# Power.net
KiCad netlist of a schematic drawn in Altium Designer
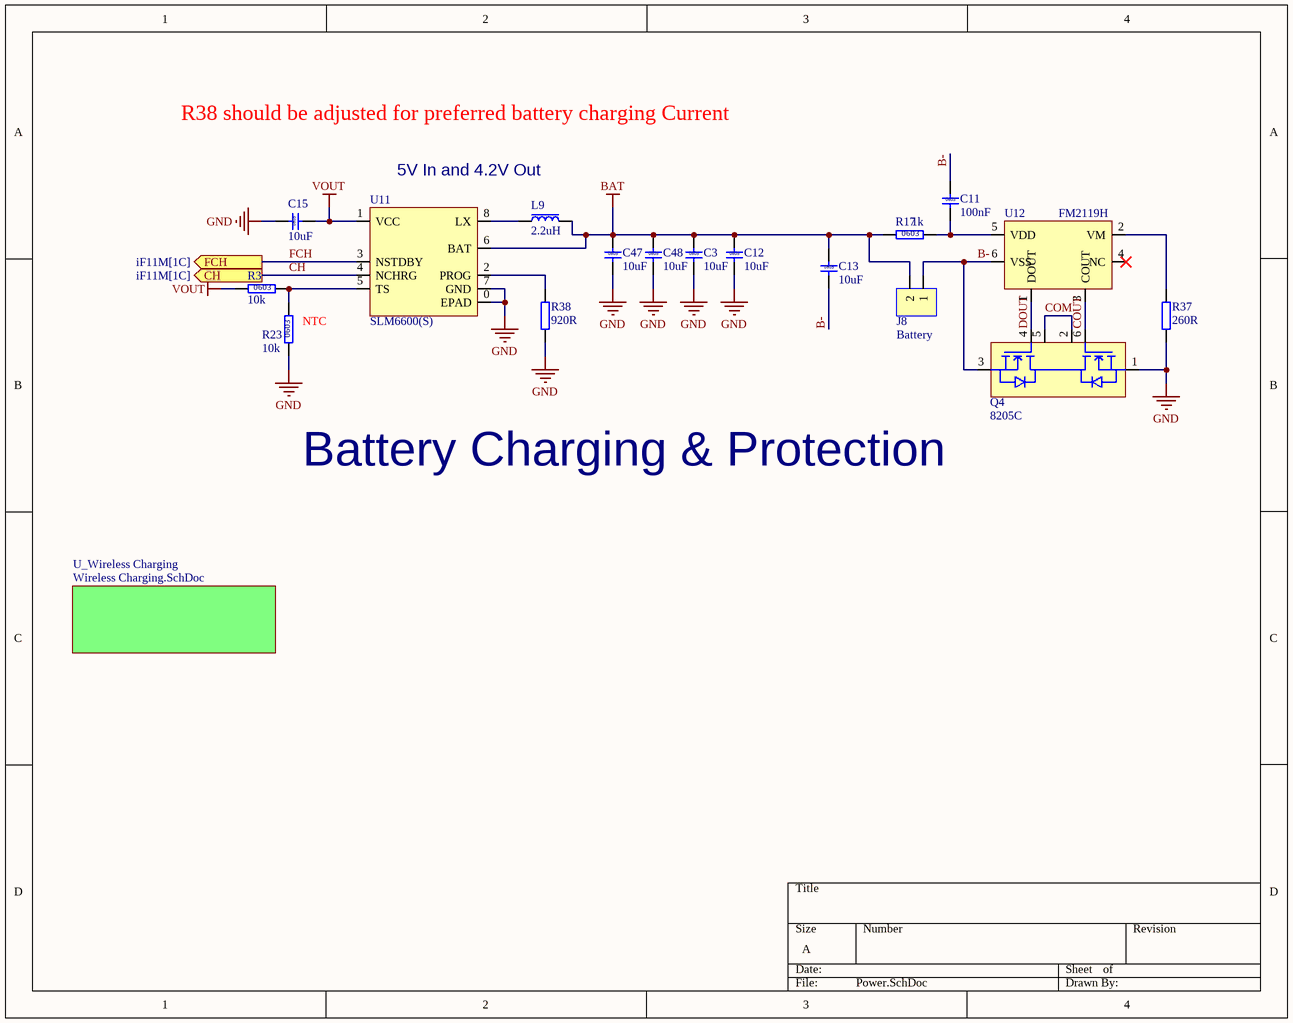
[diagram p0: Power.SchDoc]

(export (version "E")
  (design (tool "Eeschema 10.0.6"))
  (components
    (comp (ref "C3")
      (value "10uF")
      (footprint "C0805")
      (description "10% 16V")
      (fields (field (name "PART NO") "WP0005367"))
      (libsource (lib "Rescap") (part "C 0805 22uF 16V"))
    )
    (comp (ref "C11")
      (value "100nF")
      (footprint "C0603")
      (description "10% 50V")
      (fields (field (name "PART NO") "W-T-CA-X703N100K50VNT") (field (name "MANUFACTURER") "FENGHUA"))
      (libsource (lib "Rescap") (part "C 0603 100nF 50V"))
    )
    (comp (ref "C12")
      (value "10uF")
      (footprint "C0805")
      (description "10% 16V")
      (fields (field (name "PART NO") "WP0005367"))
      (libsource (lib "Rescap") (part "C 0805 22uF 16V"))
    )
    (comp (ref "C13")
      (value "10uF")
      (footprint "C0805")
      (description "10% 16V")
      (fields (field (name "PART NO") "WP0005367"))
      (libsource (lib "Rescap") (part "C 0805 22uF 16V"))
    )
    (comp (ref "C15")
      (value "10uF")
      (footprint "C0805")
      (description "10% 25V")
      (fields (field (name "PART NO") "WP0005368"))
      (libsource (lib "Rescap") (part "C 0805 10uF 25V"))
    )
    (comp (ref "C47")
      (value "10uF")
      (footprint "C0805")
      (description "10% 16V")
      (fields (field (name "PART NO") "WP0005367"))
      (libsource (lib "Rescap") (part "C 0805 22uF 16V"))
    )
    (comp (ref "C48")
      (value "10uF")
      (footprint "C0805")
      (description "10% 16V")
      (fields (field (name "PART NO") "WP0005367"))
      (libsource (lib "Rescap") (part "C 0805 22uF 16V"))
    )
    (comp (ref "J8")
      (value "Battery")
      (footprint "B2B-PH-2mm")
      (description "B2B PH 1X2 2 Pin B2B Connector")
      (libsource (lib "Connector") (part "B2B-PH-2MM"))
    )
    (comp (ref "L9")
      (value "2.2uH")
      (footprint "CD54")
      (description "SMD Inductor 2.2 uH CD54")
      (libsource (lib "Inductor") (part "CD54"))
    )
    (comp (ref "Q4")
      (value "8205C")
      (footprint "SOT23-6")
      (description "20V N-channel enhancement MOS field effect transistor")
      (libsource (lib "Transistor") (part "JST8205S"))
    )
    (comp (ref "R3")
      (value "10k")
      (footprint "R0603-LD")
      (description "5%")
      (fields (field (name "PART NO") "W-T-RE-RS03K103JT") (field (name "MANUFACTURER") "热敏D541V11增加1颗用量"))
      (libsource (lib "Rescap") (part "R 0603 10k"))
    )
    (comp (ref "R17")
      (value "1k")
      (footprint "R0603-LD")
      (description "5%")
      (fields (field (name "PART NO") "W-T-RE-RS03K102JT") (field (name "MANUFACTURER") "LAGEO"))
      (libsource (lib "Rescap") (part "R 0603 1k"))
    )
    (comp (ref "R23")
      (value "10k")
      (footprint "R0603-LD")
      (description "5%")
      (fields (field (name "PART NO") "W-T-RE-RS03K103JT") (field (name "MANUFACTURER") "热敏D541V11增加1颗用量"))
      (libsource (lib "Rescap") (part "R 0603 10k"))
    )
    (comp (ref "R37") (value "260R") (footprint "R0603") (libsource (lib "Resistor") (part "Resistor")))
    (comp (ref "R38") (value "920R") (footprint "R0603") (libsource (lib "Resistor") (part "Resistor")))
    (comp (ref "U11")
      (value "SLM6600(S)")
      (footprint "SOP-8 - EPAD")
      (libsource (lib "mylib2") (part "SLM6600(S)"))
    )
    (comp (ref "U12") (value "FM2119H") (footprint "SOT23-6") (libsource (lib "mylib2") (part "FM2119H")))
  )
  (nets
    (net (code "1") (name "/B-") (class "Default")
      (node (ref "C11") (pin "1") (pinfunction "1_1") (pintype "passive"))
      (node (ref "C13") (pin "2") (pinfunction "2_2") (pintype "passive"))
      (node (ref "J8") (pin "1") (pinfunction "1_1") (pintype "passive"))
      (node (ref "Q4") (pin "3") (pinfunction "S2_3") (pintype "passive"))
      (node (ref "U12") (pin "6") (pinfunction "VSS_6") (pintype "passive"))
    )
    (net (code "2") (name "/CH") (class "Default")
      (node (ref "U11") (pin "4") (pinfunction "NCHRG_4") (pintype "passive"))
    )
    (net (code "3") (name "/COM") (class "Default")
      (node (ref "Q4") (pin "2") (pinfunction "D1_2") (pintype "passive"))
      (node (ref "Q4") (pin "5") (pinfunction "D2_5") (pintype "passive"))
    )
    (net (code "4") (name "/COUT") (class "Default")
      (node (ref "Q4") (pin "6") (pinfunction "G1_6") (pintype "passive"))
      (node (ref "U12") (pin "3") (pinfunction "COUT_3") (pintype "passive"))
    )
    (net (code "5") (name "/DOUT") (class "Default")
      (node (ref "Q4") (pin "4") (pinfunction "G2_4") (pintype "passive"))
      (node (ref "U12") (pin "1") (pinfunction "DOUT_1") (pintype "passive"))
    )
    (net (code "6") (name "/FCH") (class "Default")
      (node (ref "U11") (pin "3") (pinfunction "NSTDBY_3") (pintype "passive"))
    )
    (net (code "7") (name "BAT") (class "Default")
      (node (ref "C12") (pin "1") (pinfunction "1_1") (pintype "passive"))
      (node (ref "C13") (pin "1") (pinfunction "1_1") (pintype "passive"))
      (node (ref "C3") (pin "1") (pinfunction "1_1") (pintype "passive"))
      (node (ref "C47") (pin "1") (pinfunction "1_1") (pintype "passive"))
      (node (ref "C48") (pin "1") (pinfunction "1_1") (pintype "passive"))
      (node (ref "J8") (pin "2") (pinfunction "2_2") (pintype "passive"))
      (node (ref "L9") (pin "2") (pinfunction "2_2") (pintype "passive"))
      (node (ref "R17") (pin "1") (pinfunction "1_1") (pintype "passive"))
      (node (ref "U11") (pin "6") (pinfunction "BAT_6") (pintype "passive"))
    )
    (net (code "8") (name "GND") (class "Default")
      (node (ref "C12") (pin "2") (pinfunction "2_2") (pintype "passive"))
      (node (ref "C15") (pin "1") (pinfunction "1_1") (pintype "passive"))
      (node (ref "C3") (pin "2") (pinfunction "2_2") (pintype "passive"))
      (node (ref "C47") (pin "2") (pinfunction "2_2") (pintype "passive"))
      (node (ref "C48") (pin "2") (pinfunction "2_2") (pintype "passive"))
      (node (ref "Q4") (pin "1") (pinfunction "S1_1") (pintype "passive"))
      (node (ref "R23") (pin "1") (pinfunction "1_1") (pintype "passive"))
      (node (ref "R37") (pin "1") (pinfunction "1_1") (pintype "passive"))
      (node (ref "R38") (pin "1") (pinfunction "1_1") (pintype "passive"))
      (node (ref "U11") (pin "0") (pinfunction "EPAD_0") (pintype "passive"))
      (node (ref "U11") (pin "7") (pinfunction "GND_7") (pintype "passive"))
    )
    (net (code "9") (name "Net-(Q4-D)") (class "Default")
      (node (ref "Q4") (pin "1") (pinfunction "D_1") (pintype "passive"))
    )
    (net (code "10") (name "Net-(U11-LX)") (class "Default")
      (node (ref "L9") (pin "1") (pinfunction "1_1") (pintype "passive"))
      (node (ref "U11") (pin "8") (pinfunction "LX_8") (pintype "passive"))
    )
    (net (code "11") (name "Net-(U11-PROG)") (class "Default")
      (node (ref "R38") (pin "2") (pinfunction "2_2") (pintype "passive"))
      (node (ref "U11") (pin "2") (pinfunction "PROG_2") (pintype "passive"))
    )
    (net (code "12") (name "Net-(U11-TS)") (class "Default")
      (node (ref "R23") (pin "2") (pinfunction "2_2") (pintype "passive"))
      (node (ref "R3") (pin "2") (pinfunction "2_2") (pintype "passive"))
      (node (ref "U11") (pin "5") (pinfunction "TS_5") (pintype "passive"))
    )
    (net (code "13") (name "Net-(U12-VDD)") (class "Default")
      (node (ref "C11") (pin "2") (pinfunction "2_2") (pintype "passive"))
      (node (ref "R17") (pin "2") (pinfunction "2_2") (pintype "passive"))
      (node (ref "U12") (pin "5") (pinfunction "VDD_5") (pintype "passive"))
    )
    (net (code "14") (name "Net-(U12-VM)") (class "Default")
      (node (ref "R37") (pin "2") (pinfunction "2_2") (pintype "passive"))
      (node (ref "U12") (pin "2") (pinfunction "VM_2") (pintype "passive"))
    )
    (net (code "15") (name "VOUT") (class "Default")
      (node (ref "C15") (pin "2") (pinfunction "2_2") (pintype "passive"))
      (node (ref "R3") (pin "1") (pinfunction "1_1") (pintype "passive"))
      (node (ref "U11") (pin "1") (pinfunction "VCC_1") (pintype "passive"))
    )
    (net (code "16") (name "unconnected-(U12-NC-Pad4)") (class "Default")
      (node (ref "U12") (pin "4") (pinfunction "NC_4") (pintype "passive+no_connect"))
    )
  )
)
